# OSO-SWAT-A1-01.net
KiCad netlist of a schematic drawn in EAGLE
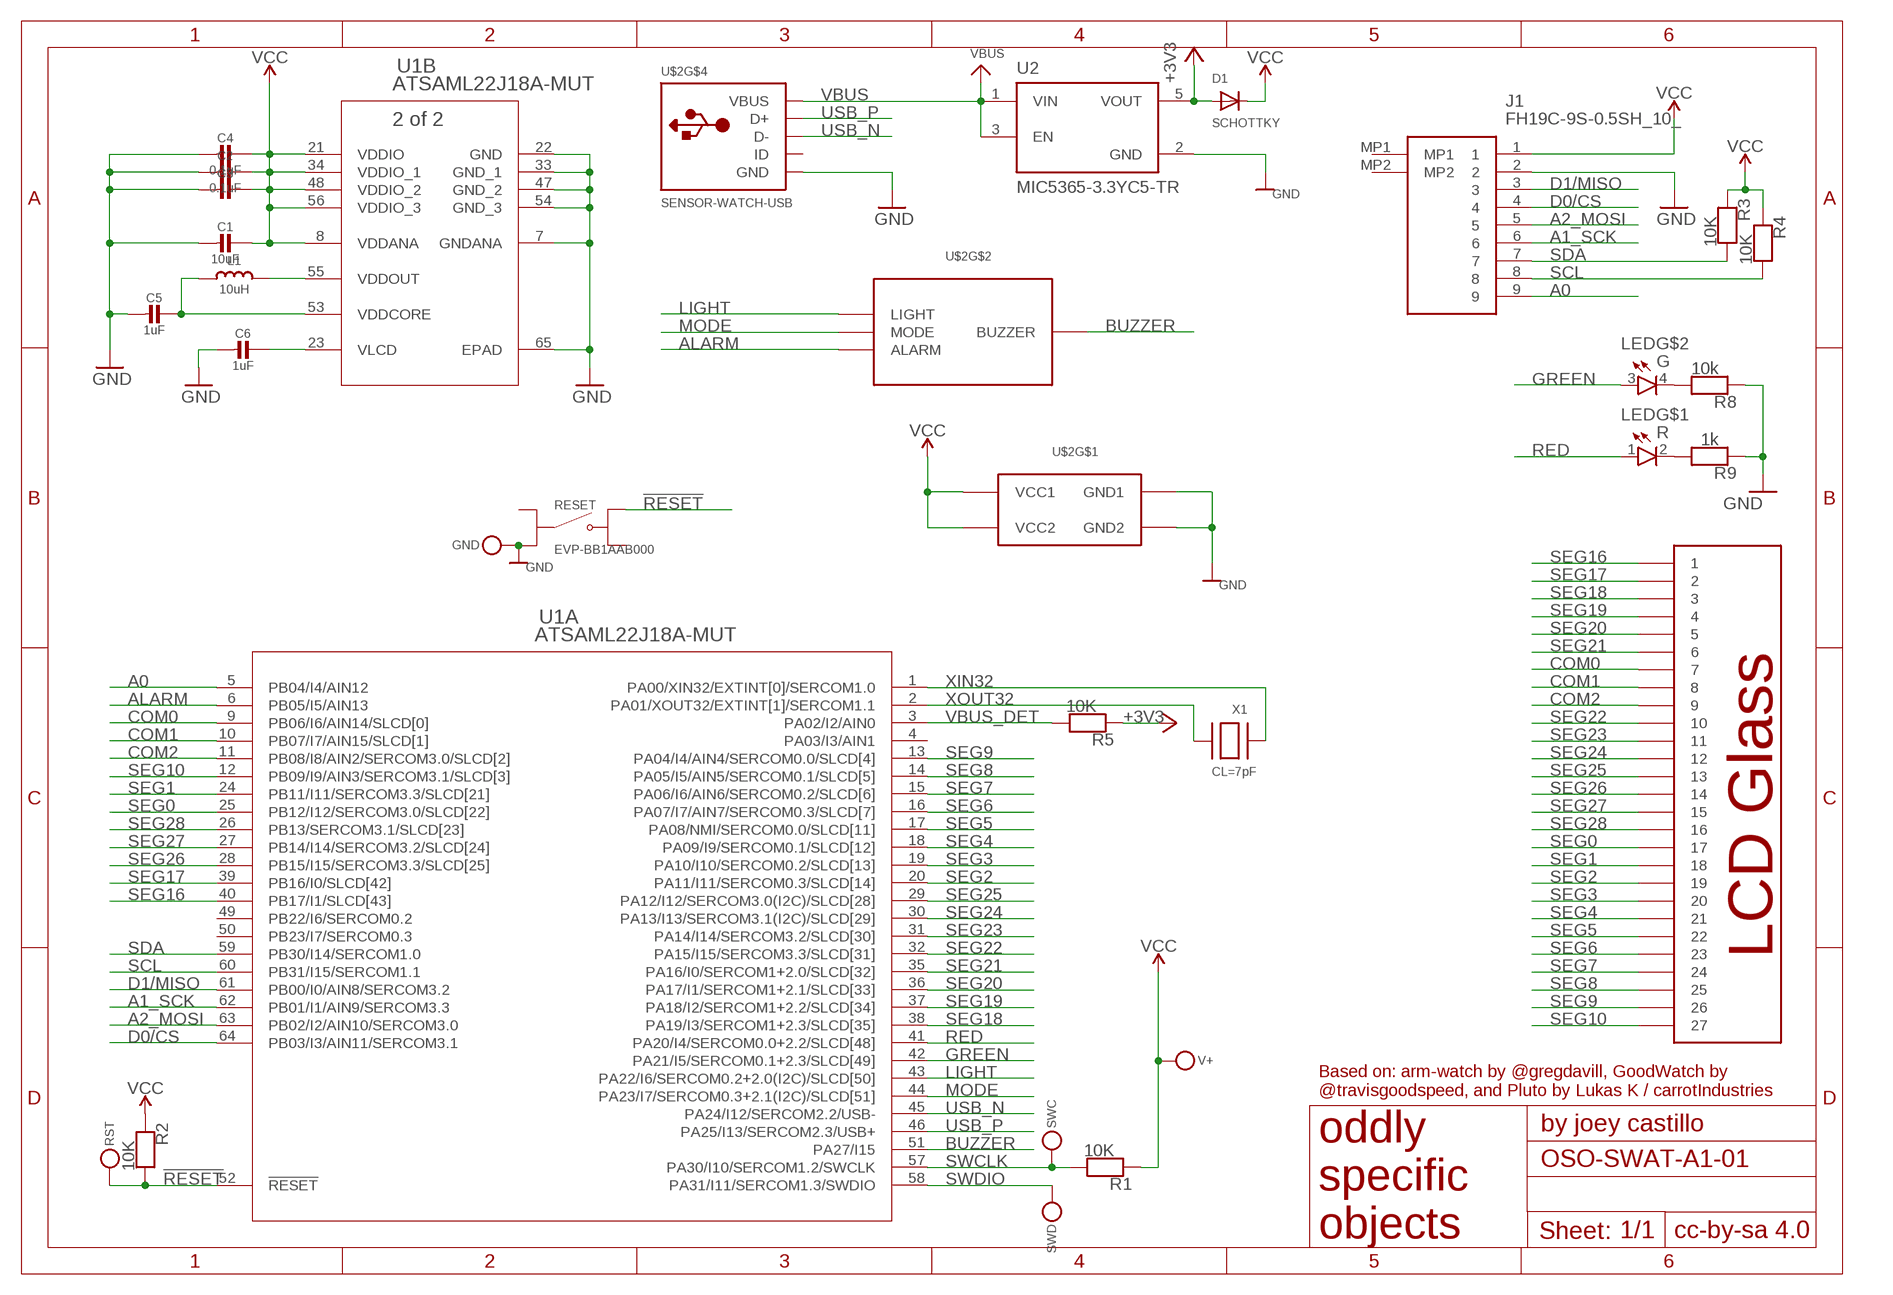
[diagram p0: schematic, sheet 1]

(export (version "E")
  (design (tool "Eeschema 10.0.6"))
  (components
    (comp (ref "C1")
      (value "10uF")
      (footprint "eagle-import:_0603MP")
      (libsource (lib "eagle-import") (part "CAP_CERAMIC_0603MP"))
    )
    (comp (ref "C2")
      (value "0.1uF")
      (footprint "eagle-import:_0603MP")
      (libsource (lib "eagle-import") (part "CAP_CERAMIC_0603MP"))
    )
    (comp (ref "C3")
      (value "0.1uF")
      (footprint "eagle-import:_0603MP")
      (libsource (lib "eagle-import") (part "CAP_CERAMIC_0603MP"))
    )
    (comp (ref "C4")
      (value "0.1uF")
      (footprint "eagle-import:_0603MP")
      (libsource (lib "eagle-import") (part "CAP_CERAMIC_0603MP"))
    )
    (comp (ref "C5")
      (value "1uF")
      (footprint "eagle-import:_0603MP")
      (libsource (lib "eagle-import") (part "CAP_CERAMIC_0603MP"))
    )
    (comp (ref "C6")
      (value "1uF")
      (footprint "eagle-import:_0603MP")
      (libsource (lib "eagle-import") (part "CAP_CERAMIC_0603MP"))
    )
    (comp (ref "D1")
      (value "SCHOTTKY")
      (footprint "eagle-import:SOD-323F")
      (libsource (lib "eagle-import") (part "DIODESOD-323F"))
    )
    (comp (ref "GND")
      (value "MICROBUILDER_TESTPOINTROUND1.5MM")
      (footprint "eagle-import:MICROBUILDER_TESTPOINT_ROUND_1.5MM")
      (libsource (lib "eagle-import") (part "MICROBUILDER_TESTPOINTROUND1.5MM"))
    )
    (comp (ref "J1")
      (value "FH19C-9S-0.5SH_10_")
      (footprint "eagle-import:FH19C9S05SH10")
      (fields
        (field (name "MANUFACTURER_PART_NUMBER") "FH19C-9S-0.5SH(10)")
        (field (name "MOUSER_PART_NUMBER") "798-FH19C9S05SH10")
      )
      (libsource (lib "eagle-import") (part "FH19C-9S-0.5SH_10_"))
    )
    (comp (ref "L1")
      (value "10uH")
      (footprint "eagle-import:MICROBUILDER__0805MP")
      (libsource (lib "eagle-import") (part "MICROBUILDER_INDUCTOR_0805MP"))
    )
    (comp (ref "LED")
      (value "QBLP655R")
      (footprint "eagle-import:LED_QBLP655R")
      (fields
        (field (name "DIGI-KEY_PART_NUMBER") "160-2026-1-ND")
        (field (name "MF") "Lite-On Inc.")
        (field (name "MP") "LTST-C235KGKRKT")
      )
      (libsource (lib "eagle-import") (part "QBLP655R"))
    )
    (comp (ref "R1")
      (value "10K")
      (footprint "eagle-import:_0603MP")
      (libsource (lib "eagle-import") (part "RESISTOR_0603MP"))
    )
    (comp (ref "R2")
      (value "10K")
      (footprint "eagle-import:_0603MP")
      (libsource (lib "eagle-import") (part "RESISTOR_0603MP"))
    )
    (comp (ref "R3")
      (value "10K")
      (footprint "eagle-import:_0603MP")
      (libsource (lib "eagle-import") (part "RESISTOR_0603MP"))
    )
    (comp (ref "R4")
      (value "10K")
      (footprint "eagle-import:_0603MP")
      (libsource (lib "eagle-import") (part "RESISTOR_0603MP"))
    )
    (comp (ref "R5")
      (value "10K")
      (footprint "eagle-import:_0603MP")
      (libsource (lib "eagle-import") (part "RESISTOR_0603MP"))
    )
    (comp (ref "R8")
      (value "10k")
      (footprint "eagle-import:_0603MP")
      (libsource (lib "eagle-import") (part "RESISTOR_0603MP"))
    )
    (comp (ref "R9")
      (value "1k")
      (footprint "eagle-import:_0603MP")
      (libsource (lib "eagle-import") (part "RESISTOR_0603MP"))
    )
    (comp (ref "RESET")
      (value "EVP-BB1AAB000")
      (footprint "eagle-import:SW_EVP-BB1AAB000")
      (fields
        (field (name "DIGI-KEY_PART_NUMBER") "P124390CT-ND")
        (field (name "MF") "Panasonic Electronic Components")
      )
      (libsource (lib "eagle-import") (part "EVP-BB1AAB000"))
    )
    (comp (ref "RST")
      (value "MICROBUILDER_TESTPOINTROUND1.5MM")
      (footprint "eagle-import:MICROBUILDER_TESTPOINT_ROUND_1.5MM")
      (libsource (lib "eagle-import") (part "MICROBUILDER_TESTPOINTROUND1.5MM"))
    )
    (comp (ref "SWC")
      (value "MICROBUILDER_TESTPOINTROUND1.5MM")
      (footprint "eagle-import:MICROBUILDER_TESTPOINT_ROUND_1.5MM")
      (libsource (lib "eagle-import") (part "MICROBUILDER_TESTPOINTROUND1.5MM"))
    )
    (comp (ref "SWD")
      (value "MICROBUILDER_TESTPOINTROUND1.5MM")
      (footprint "eagle-import:MICROBUILDER_TESTPOINT_ROUND_1.5MM")
      (libsource (lib "eagle-import") (part "MICROBUILDER_TESTPOINTROUND1.5MM"))
    )
    (comp (ref "U$2")
      (value "SENSOR-WATCH-USB")
      (footprint "eagle-import:CASIO-F91W-OUTLINE-USB")
      (libsource (lib "eagle-import") (part "SENSOR-WATCH-USB"))
    )
    (comp (ref "U1")
      (value "ATSAML22J18A-MUT")
      (footprint "eagle-import:QFN64_9X9MC_MCH")
      (fields (field (name "COPYRIGHT") "Copyright (C) 2018 Accelerated Designs. All rights reserved"))
      (libsource (lib "eagle-import") (part "ATSAML22J18A-MUT"))
    )
    (comp (ref "U2")
      (value "MIC5365-3.3YC5-TR")
      (footprint "eagle-import:SOT65P210X110-5N")
      (fields (field (name "DIGI-KEY_PART_NUMBER") "576-3193-1-ND") (field (name "MF") "Microchip"))
      (libsource (lib "eagle-import") (part "MIC5365-3.3YC5-TR"))
    )
    (comp (ref "V+")
      (value "MICROBUILDER_TESTPOINTROUND1.5MM")
      (footprint "eagle-import:MICROBUILDER_TESTPOINT_ROUND_1.5MM")
      (libsource (lib "eagle-import") (part "MICROBUILDER_TESTPOINTROUND1.5MM"))
    )
    (comp (ref "X1")
      (value "CL=7pF")
      (footprint "eagle-import:XTAL3215")
      (libsource (lib "eagle-import") (part "XTAL-3.2X1.5"))
    )
  )
  (nets
    (net (code "1") (name "+3V3") (class "Default")
      (node (ref "D1") (pin "A") (pinfunction "A_A") (pintype "passive"))
      (node (ref "R5") (pin "1") (pinfunction "1_1") (pintype "passive"))
      (node (ref "U2") (pin "5") (pinfunction "VOUT_5") (pintype "output"))
    )
    (net (code "2") (name "/A0") (class "Default")
      (node (ref "J1") (pin "9") (pinfunction "9_9") (pintype "bidirectional"))
      (node (ref "U1") (pin "5") (pinfunction "PB04/I4/AIN12_5") (pintype "bidirectional"))
    )
    (net (code "3") (name "/A1_SCK") (class "Default")
      (node (ref "J1") (pin "6") (pinfunction "6_6") (pintype "bidirectional"))
      (node (ref "U1") (pin "62") (pinfunction "PB01/I1/AIN9/SERCOM3.3_62") (pintype "bidirectional"))
    )
    (net (code "4") (name "/A2_MOSI") (class "Default")
      (node (ref "J1") (pin "5") (pinfunction "5_5") (pintype "bidirectional"))
      (node (ref "U1") (pin "63") (pinfunction "PB02/I2/AIN10/SERCOM3.0_63") (pintype "bidirectional"))
    )
    (net (code "5") (name "/ALARM") (class "Default")
      (node (ref "U$2") (pin "ALARM") (pinfunction "ALARM_ALARM") (pintype "bidirectional"))
      (node (ref "U1") (pin "6") (pinfunction "PB05/I5/AIN13_6") (pintype "bidirectional"))
    )
    (net (code "6") (name "/BUZZER") (class "Default")
      (node (ref "U$2") (pin "BUZZER") (pinfunction "BUZZER_BUZZER") (pintype "bidirectional"))
      (node (ref "U1") (pin "51") (pinfunction "PA27/I15_51") (pintype "bidirectional"))
    )
    (net (code "7") (name "/COM0") (class "Default")
      (node (ref "U$2") (pin "7") (pinfunction "7_7") (pintype "input"))
      (node (ref "U1") (pin "9") (pinfunction "PB06/I6/AIN14/SLCD[0]_9") (pintype "bidirectional"))
    )
    (net (code "8") (name "/COM1") (class "Default")
      (node (ref "U$2") (pin "8") (pinfunction "8_8") (pintype "input"))
      (node (ref "U1") (pin "10") (pinfunction "PB07/I7/AIN15/SLCD[1]_10") (pintype "bidirectional"))
    )
    (net (code "9") (name "/COM2") (class "Default")
      (node (ref "U$2") (pin "9") (pinfunction "9_9") (pintype "input"))
      (node (ref "U1") (pin "11") (pinfunction "PB08/I8/AIN2/SERCOM3.0/SLCD[2]_11") (pintype "bidirectional"))
    )
    (net (code "10") (name "/D0{slash}CS") (class "Default")
      (node (ref "J1") (pin "4") (pinfunction "4_4") (pintype "bidirectional"))
      (node (ref "U1") (pin "64") (pinfunction "PB03/I3/AIN11/SERCOM3.1_64") (pintype "bidirectional"))
    )
    (net (code "11") (name "/D1{slash}MISO") (class "Default")
      (node (ref "J1") (pin "3") (pinfunction "3_3") (pintype "bidirectional"))
      (node (ref "U1") (pin "61") (pinfunction "PB00/I0/AIN8/SERCOM3.2_61") (pintype "bidirectional"))
    )
    (net (code "12") (name "/GREEN") (class "Default")
      (node (ref "LED") (pin "3") (pinfunction "A_3") (pintype "passive"))
      (node (ref "U1") (pin "42") (pinfunction "PA21/I5/SERCOM0.1+2.3/SLCD[49]_42") (pintype "bidirectional"))
    )
    (net (code "13") (name "/LIGHT") (class "Default")
      (node (ref "U$2") (pin "LIGHT") (pinfunction "LIGHT_LIGHT") (pintype "bidirectional"))
      (node (ref "U1") (pin "43") (pinfunction "PA22/I6/SERCOM0.2+2.0(I2C)/SLCD[50]_43") (pintype "bidirectional"))
    )
    (net (code "14") (name "/MODE") (class "Default")
      (node (ref "U$2") (pin "MODE") (pinfunction "MODE_MODE") (pintype "bidirectional"))
      (node (ref "U1") (pin "44") (pinfunction "PA23/I7/SERCOM0.3+2.1(I2C)/SLCD[51]_44") (pintype "bidirectional"))
    )
    (net (code "15") (name "/RED") (class "Default")
      (node (ref "LED") (pin "1") (pinfunction "A_1") (pintype "passive"))
      (node (ref "U1") (pin "41") (pinfunction "PA20/I4/SERCOM0.0+2.2/SLCD[48]_41") (pintype "bidirectional"))
    )
    (net (code "16") (name "/SCL") (class "Default")
      (node (ref "J1") (pin "8") (pinfunction "8_8") (pintype "bidirectional"))
      (node (ref "R4") (pin "2") (pinfunction "2_2") (pintype "passive"))
      (node (ref "U1") (pin "60") (pinfunction "PB31/I15/SERCOM1.1_60") (pintype "bidirectional"))
    )
    (net (code "17") (name "/SDA") (class "Default")
      (node (ref "J1") (pin "7") (pinfunction "7_7") (pintype "bidirectional"))
      (node (ref "R3") (pin "2") (pinfunction "2_2") (pintype "passive"))
      (node (ref "U1") (pin "59") (pinfunction "PB30/I14/SERCOM1.0_59") (pintype "bidirectional"))
    )
    (net (code "18") (name "/SEG0") (class "Default")
      (node (ref "U$2") (pin "17") (pinfunction "17_17") (pintype "input"))
      (node (ref "U1") (pin "25") (pinfunction "PB12/I12/SERCOM3.0/SLCD[22]_25") (pintype "bidirectional"))
    )
    (net (code "19") (name "/SEG1") (class "Default")
      (node (ref "U$2") (pin "18") (pinfunction "18_18") (pintype "input"))
      (node (ref "U1") (pin "24") (pinfunction "PB11/I11/SERCOM3.3/SLCD[21]_24") (pintype "bidirectional"))
    )
    (net (code "20") (name "/SEG2") (class "Default")
      (node (ref "U$2") (pin "19") (pinfunction "19_19") (pintype "input"))
      (node (ref "U1") (pin "20") (pinfunction "PA11/I11/SERCOM0.3/SLCD[14]_20") (pintype "bidirectional"))
    )
    (net (code "21") (name "/SEG3") (class "Default")
      (node (ref "U$2") (pin "20") (pinfunction "20_20") (pintype "input"))
      (node (ref "U1") (pin "19") (pinfunction "PA10/I10/SERCOM0.2/SLCD[13]_19") (pintype "bidirectional"))
    )
    (net (code "22") (name "/SEG4") (class "Default")
      (node (ref "U$2") (pin "21") (pinfunction "21_21") (pintype "input"))
      (node (ref "U1") (pin "18") (pinfunction "PA09/I9/SERCOM0.1/SLCD[12]_18") (pintype "bidirectional"))
    )
    (net (code "23") (name "/SEG5") (class "Default")
      (node (ref "U$2") (pin "22") (pinfunction "22_22") (pintype "input"))
      (node (ref "U1") (pin "17") (pinfunction "PA08/NMI/SERCOM0.0/SLCD[11]_17") (pintype "bidirectional"))
    )
    (net (code "24") (name "/SEG6") (class "Default")
      (node (ref "U$2") (pin "23") (pinfunction "23_23") (pintype "input"))
      (node (ref "U1") (pin "16") (pinfunction "PA07/I7/AIN7/SERCOM0.3/SLCD[7]_16") (pintype "bidirectional"))
    )
    (net (code "25") (name "/SEG7") (class "Default")
      (node (ref "U$2") (pin "24") (pinfunction "24_24") (pintype "input"))
      (node (ref "U1") (pin "15") (pinfunction "PA06/I6/AIN6/SERCOM0.2/SLCD[6]_15") (pintype "bidirectional"))
    )
    (net (code "26") (name "/SEG8") (class "Default")
      (node (ref "U$2") (pin "25") (pinfunction "25_25") (pintype "input"))
      (node (ref "U1") (pin "14") (pinfunction "PA05/I5/AIN5/SERCOM0.1/SLCD[5]_14") (pintype "bidirectional"))
    )
    (net (code "27") (name "/SEG9") (class "Default")
      (node (ref "U$2") (pin "26") (pinfunction "26_26") (pintype "input"))
      (node (ref "U1") (pin "13") (pinfunction "PA04/I4/AIN4/SERCOM0.0/SLCD[4]_13") (pintype "bidirectional"))
    )
    (net (code "28") (name "/SEG10") (class "Default")
      (node (ref "U$2") (pin "27") (pinfunction "27_27") (pintype "input"))
      (node (ref "U1") (pin "12") (pinfunction "PB09/I9/AIN3/SERCOM3.1/SLCD[3]_12") (pintype "bidirectional"))
    )
    (net (code "29") (name "/SEG16") (class "Default")
      (node (ref "U$2") (pin "1") (pinfunction "1_1") (pintype "input"))
      (node (ref "U1") (pin "40") (pinfunction "PB17/I1/SLCD[43]_40") (pintype "bidirectional"))
    )
    (net (code "30") (name "/SEG17") (class "Default")
      (node (ref "U$2") (pin "2") (pinfunction "2_2") (pintype "input"))
      (node (ref "U1") (pin "39") (pinfunction "PB16/I0/SLCD[42]_39") (pintype "bidirectional"))
    )
    (net (code "31") (name "/SEG18") (class "Default")
      (node (ref "U$2") (pin "3") (pinfunction "3_3") (pintype "input"))
      (node (ref "U1") (pin "38") (pinfunction "PA19/I3/SERCOM1+2.3/SLCD[35]_38") (pintype "bidirectional"))
    )
    (net (code "32") (name "/SEG19") (class "Default")
      (node (ref "U$2") (pin "4") (pinfunction "4_4") (pintype "input"))
      (node (ref "U1") (pin "37") (pinfunction "PA18/I2/SERCOM1+2.2/SLCD[34]_37") (pintype "bidirectional"))
    )
    (net (code "33") (name "/SEG20") (class "Default")
      (node (ref "U$2") (pin "5") (pinfunction "5_5") (pintype "input"))
      (node (ref "U1") (pin "36") (pinfunction "PA17/I1/SERCOM1+2.1/SLCD[33]_36") (pintype "bidirectional"))
    )
    (net (code "34") (name "/SEG21") (class "Default")
      (node (ref "U$2") (pin "6") (pinfunction "6_6") (pintype "input"))
      (node (ref "U1") (pin "35") (pinfunction "PA16/I0/SERCOM1+2.0/SLCD[32]_35") (pintype "bidirectional"))
    )
    (net (code "35") (name "/SEG22") (class "Default")
      (node (ref "U$2") (pin "10") (pinfunction "10_10") (pintype "input"))
      (node (ref "U1") (pin "32") (pinfunction "PA15/I15/SERCOM3.3/SLCD[31]_32") (pintype "bidirectional"))
    )
    (net (code "36") (name "/SEG23") (class "Default")
      (node (ref "U$2") (pin "11") (pinfunction "11_11") (pintype "input"))
      (node (ref "U1") (pin "31") (pinfunction "PA14/I14/SERCOM3.2/SLCD[30]_31") (pintype "bidirectional"))
    )
    (net (code "37") (name "/SEG24") (class "Default")
      (node (ref "U$2") (pin "12") (pinfunction "12_12") (pintype "input"))
      (node (ref "U1") (pin "30") (pinfunction "PA13/I13/SERCOM3.1(I2C)/SLCD[29]_30") (pintype "bidirectional"))
    )
    (net (code "38") (name "/SEG25") (class "Default")
      (node (ref "U$2") (pin "13") (pinfunction "13_13") (pintype "input"))
      (node (ref "U1") (pin "29") (pinfunction "PA12/I12/SERCOM3.0(I2C)/SLCD[28]_29") (pintype "bidirectional"))
    )
    (net (code "39") (name "/SEG26") (class "Default")
      (node (ref "U$2") (pin "14") (pinfunction "14_14") (pintype "input"))
      (node (ref "U1") (pin "28") (pinfunction "PB15/I15/SERCOM3.3/SLCD[25]_28") (pintype "bidirectional"))
    )
    (net (code "40") (name "/SEG27") (class "Default")
      (node (ref "U$2") (pin "15") (pinfunction "15_15") (pintype "input"))
      (node (ref "U1") (pin "27") (pinfunction "PB14/I14/SERCOM3.2/SLCD[24]_27") (pintype "bidirectional"))
    )
    (net (code "41") (name "/SEG28") (class "Default")
      (node (ref "U$2") (pin "16") (pinfunction "16_16") (pintype "input"))
      (node (ref "U1") (pin "26") (pinfunction "PB13/SERCOM3.1/SLCD[23]_26") (pintype "bidirectional"))
    )
    (net (code "42") (name "/SWCLK") (class "Default")
      (node (ref "R1") (pin "2") (pinfunction "2_2") (pintype "passive"))
      (node (ref "SWC") (pin "P$1") (pinfunction "P$1_P$1") (pintype "bidirectional"))
      (node (ref "U1") (pin "57") (pinfunction "PA30/I10/SERCOM1.2/SWCLK_57") (pintype "bidirectional"))
    )
    (net (code "43") (name "/SWDIO") (class "Default")
      (node (ref "SWD") (pin "P$1") (pinfunction "P$1_P$1") (pintype "bidirectional"))
      (node (ref "U1") (pin "58") (pinfunction "PA31/I11/SERCOM1.3/SWDIO_58") (pintype "bidirectional"))
    )
    (net (code "44") (name "/USB_N") (class "Default")
      (node (ref "U$2") (pin "USB_N") (pinfunction "D-_USB_N") (pintype "bidirectional"))
      (node (ref "U1") (pin "45") (pinfunction "PA24/I12/SERCOM2.2/USB-_45") (pintype "bidirectional"))
    )
    (net (code "45") (name "/USB_P") (class "Default")
      (node (ref "U$2") (pin "USB_P") (pinfunction "D+_USB_P") (pintype "bidirectional"))
      (node (ref "U1") (pin "46") (pinfunction "PA25/I13/SERCOM2.3/USB+_46") (pintype "bidirectional"))
    )
    (net (code "46") (name "/VBUS_DET") (class "Default")
      (node (ref "R5") (pin "2") (pinfunction "2_2") (pintype "passive"))
      (node (ref "U1") (pin "3") (pinfunction "PA02/I2/AIN0_3") (pintype "bidirectional"))
    )
    (net (code "47") (name "/XIN32") (class "Default")
      (node (ref "U1") (pin "1") (pinfunction "PA00/XIN32/EXTINT[0]/SERCOM1.0_1") (pintype "bidirectional"))
      (node (ref "X1") (pin "P$1") (pinfunction "P$1_P$1") (pintype "bidirectional"))
    )
    (net (code "48") (name "/XOUT32") (class "Default")
      (node (ref "U1") (pin "2") (pinfunction "PA01/XOUT32/EXTINT[1]/SERCOM1.1_2") (pintype "bidirectional"))
      (node (ref "X1") (pin "P$2") (pinfunction "P$2_P$2") (pintype "bidirectional"))
    )
    (net (code "49") (name "/~{RESET}") (class "Default")
      (node (ref "R2") (pin "2") (pinfunction "2_2") (pintype "passive"))
      (node (ref "RESET") (pin "B1") (pinfunction "B1_B1") (pintype "passive"))
      (node (ref "RST") (pin "P$1") (pinfunction "P$1_P$1") (pintype "bidirectional"))
      (node (ref "U1") (pin "52") (pinfunction "~{RESET}_52") (pintype "bidirectional"))
    )
    (net (code "50") (name "GND") (class "Default")
      (node (ref "C1") (pin "2") (pinfunction "2_2") (pintype "passive"))
      (node (ref "C2") (pin "2") (pinfunction "2_2") (pintype "passive"))
      (node (ref "C3") (pin "2") (pinfunction "2_2") (pintype "passive"))
      (node (ref "C4") (pin "2") (pinfunction "2_2") (pintype "passive"))
      (node (ref "C5") (pin "2") (pinfunction "2_2") (pintype "passive"))
      (node (ref "C6") (pin "2") (pinfunction "2_2") (pintype "passive"))
      (node (ref "GND") (pin "P$1") (pinfunction "P$1_P$1") (pintype "bidirectional"))
      (node (ref "J1") (pin "2") (pinfunction "2_2") (pintype "bidirectional"))
      (node (ref "R8") (pin "1") (pinfunction "1_1") (pintype "passive"))
      (node (ref "R9") (pin "1") (pinfunction "1_1") (pintype "passive"))
      (node (ref "RESET") (pin "A2") (pinfunction "A2_A2") (pintype "passive"))
      (node (ref "U$2") (pin "GND") (pinfunction "GND_GND") (pintype "power_in"))
      (node (ref "U$2") (pin "GND1") (pinfunction "GND1_GND1") (pintype "bidirectional"))
      (node (ref "U$2") (pin "GND2") (pinfunction "GND2_GND2") (pintype "bidirectional"))
      (node (ref "U1") (pin "22") (pinfunction "GND_22") (pintype "passive"))
      (node (ref "U1") (pin "33") (pinfunction "GND_1_33") (pintype "passive"))
      (node (ref "U1") (pin "47") (pinfunction "GND_2_47") (pintype "passive"))
      (node (ref "U1") (pin "54") (pinfunction "GND_3_54") (pintype "passive"))
      (node (ref "U1") (pin "65") (pinfunction "EPAD_65") (pintype "passive"))
      (node (ref "U1") (pin "7") (pinfunction "GNDANA_7") (pintype "passive"))
      (node (ref "U2") (pin "2") (pinfunction "GND_2") (pintype "power_in"))
    )
    (net (code "51") (name "Net-(LEDA-C)") (class "Default")
      (node (ref "LED") (pin "2") (pinfunction "C_2") (pintype "passive"))
      (node (ref "R9") (pin "2") (pinfunction "2_2") (pintype "passive"))
    )
    (net (code "52") (name "Net-(LEDB-C)") (class "Default")
      (node (ref "LED") (pin "4") (pinfunction "C_4") (pintype "passive"))
      (node (ref "R8") (pin "2") (pinfunction "2_2") (pintype "passive"))
    )
    (net (code "53") (name "Net-(U1B-VDDCORE)") (class "Default")
      (node (ref "C5") (pin "1") (pinfunction "1_1") (pintype "passive"))
      (node (ref "L1") (pin "1") (pinfunction "1_1") (pintype "passive"))
      (node (ref "U1") (pin "53") (pinfunction "VDDCORE_53") (pintype "power_in"))
    )
    (net (code "54") (name "Net-(U1B-VDDOUT)") (class "Default")
      (node (ref "L1") (pin "2") (pinfunction "2_2") (pintype "passive"))
      (node (ref "U1") (pin "55") (pinfunction "VDDOUT_55") (pintype "output"))
    )
    (net (code "55") (name "Net-(U1B-VLCD)") (class "Default")
      (node (ref "C6") (pin "1") (pinfunction "1_1") (pintype "passive"))
      (node (ref "U1") (pin "23") (pinfunction "VLCD_23") (pintype "passive"))
    )
    (net (code "56") (name "VBUS") (class "Default")
      (node (ref "U$2") (pin "VBUS") (pinfunction "VBUS_VBUS") (pintype "power_in"))
      (node (ref "U2") (pin "1") (pinfunction "VIN_1") (pintype "input"))
      (node (ref "U2") (pin "3") (pinfunction "EN_3") (pintype "input"))
    )
    (net (code "57") (name "VCC") (class "Default")
      (node (ref "C1") (pin "1") (pinfunction "1_1") (pintype "passive"))
      (node (ref "C2") (pin "1") (pinfunction "1_1") (pintype "passive"))
      (node (ref "C3") (pin "1") (pinfunction "1_1") (pintype "passive"))
      (node (ref "C4") (pin "1") (pinfunction "1_1") (pintype "passive"))
      (node (ref "D1") (pin "C") (pinfunction "C_C") (pintype "passive"))
      (node (ref "J1") (pin "1") (pinfunction "1_1") (pintype "bidirectional"))
      (node (ref "R1") (pin "1") (pinfunction "1_1") (pintype "passive"))
      (node (ref "R2") (pin "1") (pinfunction "1_1") (pintype "passive"))
      (node (ref "R3") (pin "1") (pinfunction "1_1") (pintype "passive"))
      (node (ref "R4") (pin "1") (pinfunction "1_1") (pintype "passive"))
      (node (ref "U$2") (pin "VCC1") (pinfunction "VCC1_VCC1") (pintype "bidirectional"))
      (node (ref "U$2") (pin "VCC2") (pinfunction "VCC2_VCC2") (pintype "bidirectional"))
      (node (ref "U1") (pin "21") (pinfunction "VDDIO_21") (pintype "power_in"))
      (node (ref "U1") (pin "34") (pinfunction "VDDIO_1_34") (pintype "power_in"))
      (node (ref "U1") (pin "48") (pinfunction "VDDIO_2_48") (pintype "power_in"))
      (node (ref "U1") (pin "56") (pinfunction "VDDIO_3_56") (pintype "power_in"))
      (node (ref "U1") (pin "8") (pinfunction "VDDANA_8") (pintype "power_in"))
      (node (ref "V+") (pin "P$1") (pinfunction "P$1_P$1") (pintype "bidirectional"))
    )
    (net (code "58") (name "unconnected-(J1-PadMP1)") (class "Default")
      (node (ref "J1") (pin "MP1") (pinfunction "MP1_MP1") (pintype "bidirectional"))
    )
    (net (code "59") (name "unconnected-(J1-PadMP2)") (class "Default")
      (node (ref "J1") (pin "MP2") (pinfunction "MP2_MP2") (pintype "bidirectional"))
    )
    (net (code "60") (name "unconnected-(RESET-PadA1)") (class "Default")
      (node (ref "RESET") (pin "A1") (pinfunction "A1_A1") (pintype "passive"))
    )
    (net (code "61") (name "unconnected-(RESET-PadB2)") (class "Default")
      (node (ref "RESET") (pin "B2") (pinfunction "B2_B2") (pintype "passive"))
    )
    (net (code "62") (name "unconnected-(U$2D-ID-PadUSB_ID)") (class "Default")
      (node (ref "U$2") (pin "USB_ID") (pinfunction "ID_USB_ID") (pintype "bidirectional"))
    )
    (net (code "63") (name "unconnected-(U1A-PA03{slash}I3{slash}AIN1-Pad4)") (class "Default")
      (node (ref "U1") (pin "4") (pinfunction "PA03/I3/AIN1_4") (pintype "bidirectional"))
    )
    (net (code "64") (name "unconnected-(U1A-PB22{slash}I6{slash}SERCOM0.2-Pad49)") (class "Default")
      (node (ref "U1") (pin "49") (pinfunction "PB22/I6/SERCOM0.2_49") (pintype "bidirectional"))
    )
    (net (code "65") (name "unconnected-(U1A-PB23{slash}I7{slash}SERCOM0.3-Pad50)") (class "Default")
      (node (ref "U1") (pin "50") (pinfunction "PB23/I7/SERCOM0.3_50") (pintype "bidirectional"))
    )
  )
)
